# ATMEGA16L-8PI.net
KiCad netlist of a schematic drawn in Altium Designer
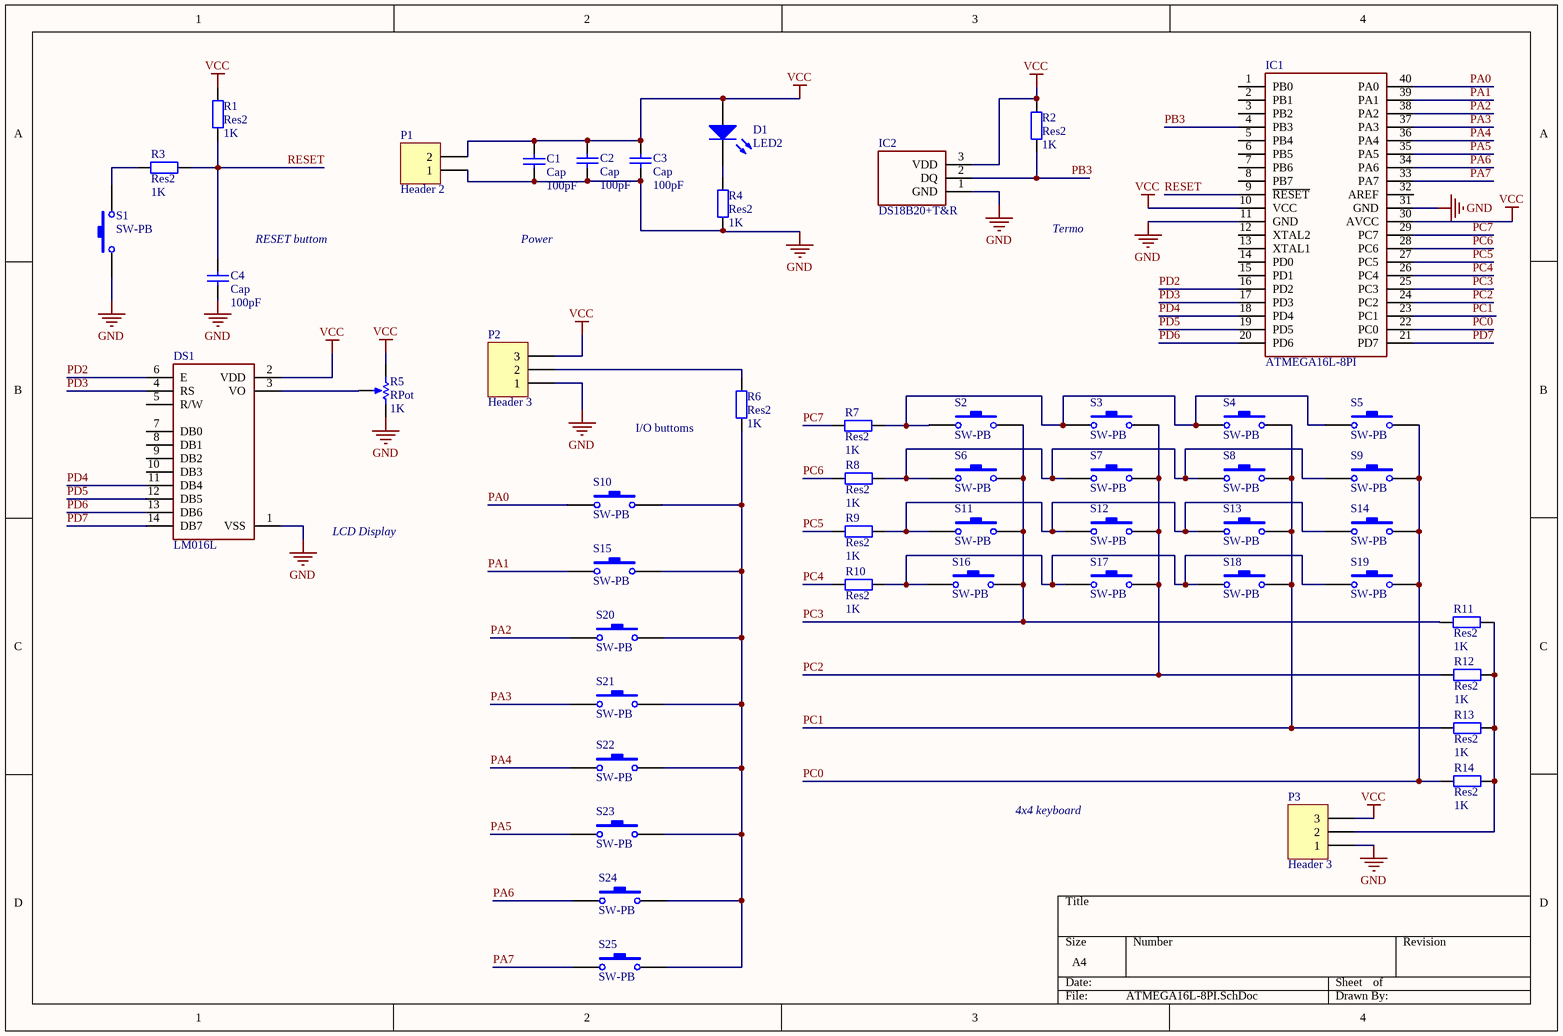
[diagram p0: ATMEGA16L-8PI.SchDoc]

(export (version "E")
  (design (tool "Eeschema 10.0.6"))
  (components
    (comp (ref "C1")
      (value "Cap")
      (footprint "RAD-0.3")
      (description "Capacitor")
      (fields (field (name "ALTIUM_VALUE") "100pF") (field (name "PUBLISHER") "Altium Limited"))
      (libsource (lib "Miscellaneous Devices") (part "Cap"))
    )
    (comp (ref "C2")
      (value "Cap")
      (footprint "RAD-0.3")
      (description "Capacitor")
      (fields (field (name "ALTIUM_VALUE") "100pF") (field (name "PUBLISHER") "Altium Limited"))
      (libsource (lib "Miscellaneous Devices") (part "Cap"))
    )
    (comp (ref "C3")
      (value "Cap")
      (footprint "RAD-0.3")
      (description "Capacitor")
      (fields (field (name "ALTIUM_VALUE") "100pF") (field (name "PUBLISHER") "Altium Limited"))
      (libsource (lib "Miscellaneous Devices") (part "Cap"))
    )
    (comp (ref "C4")
      (value "Cap")
      (footprint "RAD-0.3")
      (description "Capacitor")
      (fields (field (name "ALTIUM_VALUE") "100pF") (field (name "PUBLISHER") "Altium Limited"))
      (libsource (lib "Miscellaneous Devices") (part "Cap"))
    )
    (comp (ref "D1")
      (value "LED2")
      (footprint "3.2X1.6X1.1")
      (description "Typical RED, GREEN, YELLOW, AMBER GaAs LED")
      (fields (field (name "PUBLISHER") "Altium Limited"))
      (libsource (lib "Miscellaneous Devices") (part "LED2"))
    )
    (comp (ref "DS1")
      (value "LM016L")
      (footprint "PcbLib1:LCD_LM016L")
      (description "Display Lcd 35x75mm")
      (fields (field (name "MF") "Hitachi"))
      (libsource (lib "Schlib1") (part "LM016L"))
    )
    (comp (ref "IC1")
      (value "ATMEGA16L-8PI")
      (footprint "PcbLib1:DIP1556W56P254L5232H483Q40N")
      (description "Integrated Circuit")
      (fields (field (name "MOUSER PART NUMBER") "556-ATMEGA16L-8PI"))
      (libsource (lib "Schlib1") (part "ATMEGA16L-8PI"))
    )
    (comp (ref "IC2")
      (value "DS18B20+T&R")
      (footprint "PcbLib1:DS18B20TR")
      (description "Integrated Circuit")
      (fields (field (name "MOUSER PART NUMBER") "700-DS18B20T&R"))
      (libsource (lib "Schlib1") (part "DS18B20+T&R"))
    )
    (comp (ref "P1")
      (value "Header 2")
      (footprint "HDR1X2")
      (description "Header, 2-Pin")
      (fields (field (name "PUBLISHER") "Altium Limited"))
      (libsource (lib "Miscellaneous Connectors") (part "Header 2"))
    )
    (comp (ref "P2")
      (value "Header 3")
      (footprint "HDR1X3")
      (description "Header, 3-Pin")
      (fields (field (name "PUBLISHER") "Altium Limited"))
      (libsource (lib "Miscellaneous Connectors") (part "Header 3"))
    )
    (comp (ref "P3")
      (value "Header 3")
      (footprint "HDR1X3")
      (description "Header, 3-Pin")
      (fields (field (name "PUBLISHER") "Altium Limited"))
      (libsource (lib "Miscellaneous Connectors") (part "Header 3"))
    )
    (comp (ref "R1")
      (value "Res2")
      (footprint "AXIAL-0.4")
      (description "Resistor")
      (fields (field (name "ALTIUM_VALUE") "1K") (field (name "PUBLISHER") "Altium Limited"))
      (libsource (lib "") (part "Res2_1"))
    )
    (comp (ref "R2")
      (value "Res2")
      (footprint "AXIAL-0.4")
      (description "Resistor")
      (fields (field (name "ALTIUM_VALUE") "1K") (field (name "PUBLISHER") "Altium Limited"))
      (libsource (lib "") (part "Res2_1"))
    )
    (comp (ref "R3")
      (value "Res2")
      (footprint "AXIAL-0.4")
      (description "Resistor")
      (fields (field (name "ALTIUM_VALUE") "1K") (field (name "PUBLISHER") "Altium Limited"))
      (libsource (lib "Miscellaneous Devices") (part "Res2"))
    )
    (comp (ref "R4")
      (value "Res2")
      (footprint "AXIAL-0.4")
      (description "Resistor")
      (fields (field (name "ALTIUM_VALUE") "1K") (field (name "PUBLISHER") "Altium Limited"))
      (libsource (lib "") (part "Res2_2"))
    )
    (comp (ref "R5")
      (value "RPot")
      (footprint "VR5")
      (description "Potentiometer")
      (fields (field (name "ALTIUM_VALUE") "1K") (field (name "PUBLISHER") "Altium Limited"))
      (libsource (lib "Miscellaneous Devices") (part "RPot"))
    )
    (comp (ref "R6")
      (value "Res2")
      (footprint "AXIAL-0.4")
      (description "Resistor")
      (fields (field (name "ALTIUM_VALUE") "1K") (field (name "PUBLISHER") "Altium Limited"))
      (libsource (lib "") (part "Res2_1"))
    )
    (comp (ref "R7")
      (value "Res2")
      (footprint "AXIAL-0.4")
      (description "Resistor")
      (fields (field (name "ALTIUM_VALUE") "1K") (field (name "PUBLISHER") "Altium Limited"))
      (libsource (lib "Miscellaneous Devices") (part "Res2"))
    )
    (comp (ref "R8")
      (value "Res2")
      (footprint "AXIAL-0.4")
      (description "Resistor")
      (fields (field (name "ALTIUM_VALUE") "1K") (field (name "PUBLISHER") "Altium Limited"))
      (libsource (lib "Miscellaneous Devices") (part "Res2"))
    )
    (comp (ref "R9")
      (value "Res2")
      (footprint "AXIAL-0.4")
      (description "Resistor")
      (fields (field (name "ALTIUM_VALUE") "1K") (field (name "PUBLISHER") "Altium Limited"))
      (libsource (lib "Miscellaneous Devices") (part "Res2"))
    )
    (comp (ref "R10")
      (value "Res2")
      (footprint "AXIAL-0.4")
      (description "Resistor")
      (fields (field (name "ALTIUM_VALUE") "1K") (field (name "PUBLISHER") "Altium Limited"))
      (libsource (lib "Miscellaneous Devices") (part "Res2"))
    )
    (comp (ref "R11")
      (value "Res2")
      (footprint "AXIAL-0.4")
      (description "Resistor")
      (fields (field (name "ALTIUM_VALUE") "1K") (field (name "PUBLISHER") "Altium Limited"))
      (libsource (lib "Miscellaneous Devices") (part "Res2"))
    )
    (comp (ref "R12")
      (value "Res2")
      (footprint "AXIAL-0.4")
      (description "Resistor")
      (fields (field (name "ALTIUM_VALUE") "1K") (field (name "PUBLISHER") "Altium Limited"))
      (libsource (lib "Miscellaneous Devices") (part "Res2"))
    )
    (comp (ref "R13")
      (value "Res2")
      (footprint "AXIAL-0.4")
      (description "Resistor")
      (fields (field (name "ALTIUM_VALUE") "1K") (field (name "PUBLISHER") "Altium Limited"))
      (libsource (lib "Miscellaneous Devices") (part "Res2"))
    )
    (comp (ref "R14")
      (value "Res2")
      (footprint "AXIAL-0.4")
      (description "Resistor")
      (fields (field (name "ALTIUM_VALUE") "1K") (field (name "PUBLISHER") "Altium Limited"))
      (libsource (lib "Miscellaneous Devices") (part "Res2"))
    )
    (comp (ref "S1")
      (value "SW-PB")
      (footprint "SPST-2")
      (description "Switch")
      (fields (field (name "PUBLISHER") "Altium Limited"))
      (libsource (lib "Miscellaneous Devices") (part "SW-PB"))
    )
    (comp (ref "S2")
      (value "SW-PB")
      (footprint "SPST-2")
      (description "Switch")
      (fields (field (name "PUBLISHER") "Altium Limited"))
      (libsource (lib "Miscellaneous Devices") (part "SW-PB"))
    )
    (comp (ref "S3")
      (value "SW-PB")
      (footprint "SPST-2")
      (description "Switch")
      (fields (field (name "PUBLISHER") "Altium Limited"))
      (libsource (lib "Miscellaneous Devices") (part "SW-PB"))
    )
    (comp (ref "S4")
      (value "SW-PB")
      (footprint "SPST-2")
      (description "Switch")
      (fields (field (name "PUBLISHER") "Altium Limited"))
      (libsource (lib "Miscellaneous Devices") (part "SW-PB"))
    )
    (comp (ref "S5")
      (value "SW-PB")
      (footprint "SPST-2")
      (description "Switch")
      (fields (field (name "PUBLISHER") "Altium Limited"))
      (libsource (lib "Miscellaneous Devices") (part "SW-PB"))
    )
    (comp (ref "S6")
      (value "SW-PB")
      (footprint "SPST-2")
      (description "Switch")
      (fields (field (name "PUBLISHER") "Altium Limited"))
      (libsource (lib "Miscellaneous Devices") (part "SW-PB"))
    )
    (comp (ref "S7")
      (value "SW-PB")
      (footprint "SPST-2")
      (description "Switch")
      (fields (field (name "PUBLISHER") "Altium Limited"))
      (libsource (lib "Miscellaneous Devices") (part "SW-PB"))
    )
    (comp (ref "S8")
      (value "SW-PB")
      (footprint "SPST-2")
      (description "Switch")
      (fields (field (name "PUBLISHER") "Altium Limited"))
      (libsource (lib "Miscellaneous Devices") (part "SW-PB"))
    )
    (comp (ref "S9")
      (value "SW-PB")
      (footprint "SPST-2")
      (description "Switch")
      (fields (field (name "PUBLISHER") "Altium Limited"))
      (libsource (lib "Miscellaneous Devices") (part "SW-PB"))
    )
    (comp (ref "S10")
      (value "SW-PB")
      (footprint "SPST-2")
      (description "Switch")
      (fields (field (name "PUBLISHER") "Altium Limited"))
      (libsource (lib "Miscellaneous Devices") (part "SW-PB"))
    )
    (comp (ref "S11")
      (value "SW-PB")
      (footprint "SPST-2")
      (description "Switch")
      (fields (field (name "PUBLISHER") "Altium Limited"))
      (libsource (lib "Miscellaneous Devices") (part "SW-PB"))
    )
    (comp (ref "S12")
      (value "SW-PB")
      (footprint "SPST-2")
      (description "Switch")
      (fields (field (name "PUBLISHER") "Altium Limited"))
      (libsource (lib "Miscellaneous Devices") (part "SW-PB"))
    )
    (comp (ref "S13")
      (value "SW-PB")
      (footprint "SPST-2")
      (description "Switch")
      (fields (field (name "PUBLISHER") "Altium Limited"))
      (libsource (lib "Miscellaneous Devices") (part "SW-PB"))
    )
    (comp (ref "S14")
      (value "SW-PB")
      (footprint "SPST-2")
      (description "Switch")
      (fields (field (name "PUBLISHER") "Altium Limited"))
      (libsource (lib "Miscellaneous Devices") (part "SW-PB"))
    )
    (comp (ref "S15")
      (value "SW-PB")
      (footprint "SPST-2")
      (description "Switch")
      (fields (field (name "PUBLISHER") "Altium Limited"))
      (libsource (lib "Miscellaneous Devices") (part "SW-PB"))
    )
    (comp (ref "S16")
      (value "SW-PB")
      (footprint "SPST-2")
      (description "Switch")
      (fields (field (name "PUBLISHER") "Altium Limited"))
      (libsource (lib "Miscellaneous Devices") (part "SW-PB"))
    )
    (comp (ref "S17")
      (value "SW-PB")
      (footprint "SPST-2")
      (description "Switch")
      (fields (field (name "PUBLISHER") "Altium Limited"))
      (libsource (lib "Miscellaneous Devices") (part "SW-PB"))
    )
    (comp (ref "S18")
      (value "SW-PB")
      (footprint "SPST-2")
      (description "Switch")
      (fields (field (name "PUBLISHER") "Altium Limited"))
      (libsource (lib "Miscellaneous Devices") (part "SW-PB"))
    )
    (comp (ref "S19")
      (value "SW-PB")
      (footprint "SPST-2")
      (description "Switch")
      (fields (field (name "PUBLISHER") "Altium Limited"))
      (libsource (lib "Miscellaneous Devices") (part "SW-PB"))
    )
    (comp (ref "S20")
      (value "SW-PB")
      (footprint "SPST-2")
      (description "Switch")
      (fields (field (name "PUBLISHER") "Altium Limited"))
      (libsource (lib "Miscellaneous Devices") (part "SW-PB"))
    )
    (comp (ref "S21")
      (value "SW-PB")
      (footprint "SPST-2")
      (description "Switch")
      (fields (field (name "PUBLISHER") "Altium Limited"))
      (libsource (lib "Miscellaneous Devices") (part "SW-PB"))
    )
    (comp (ref "S22")
      (value "SW-PB")
      (footprint "SPST-2")
      (description "Switch")
      (fields (field (name "PUBLISHER") "Altium Limited"))
      (libsource (lib "Miscellaneous Devices") (part "SW-PB"))
    )
    (comp (ref "S23")
      (value "SW-PB")
      (footprint "SPST-2")
      (description "Switch")
      (fields (field (name "PUBLISHER") "Altium Limited"))
      (libsource (lib "Miscellaneous Devices") (part "SW-PB"))
    )
    (comp (ref "S24")
      (value "SW-PB")
      (footprint "SPST-2")
      (description "Switch")
      (fields (field (name "PUBLISHER") "Altium Limited"))
      (libsource (lib "Miscellaneous Devices") (part "SW-PB"))
    )
    (comp (ref "S25")
      (value "SW-PB")
      (footprint "SPST-2")
      (description "Switch")
      (fields (field (name "PUBLISHER") "Altium Limited"))
      (libsource (lib "Miscellaneous Devices") (part "SW-PB"))
    )
  )
  (nets
    (net (code "1") (name "/PA0") (class "Default")
      (node (ref "IC1") (pin "40") (pinfunction "PA0_40") (pintype "passive"))
      (node (ref "S10") (pin "1") (pinfunction "1_1") (pintype "passive"))
    )
    (net (code "2") (name "/PA1") (class "Default")
      (node (ref "IC1") (pin "39") (pinfunction "PA1_39") (pintype "passive"))
      (node (ref "S15") (pin "1") (pinfunction "1_1") (pintype "passive"))
    )
    (net (code "3") (name "/PA2") (class "Default")
      (node (ref "IC1") (pin "38") (pinfunction "PA2_38") (pintype "passive"))
      (node (ref "S20") (pin "1") (pinfunction "1_1") (pintype "passive"))
    )
    (net (code "4") (name "/PA3") (class "Default")
      (node (ref "IC1") (pin "37") (pinfunction "PA3_37") (pintype "passive"))
      (node (ref "S21") (pin "1") (pinfunction "1_1") (pintype "passive"))
    )
    (net (code "5") (name "/PA4") (class "Default")
      (node (ref "IC1") (pin "36") (pinfunction "PA4_36") (pintype "passive"))
      (node (ref "S22") (pin "1") (pinfunction "1_1") (pintype "passive"))
    )
    (net (code "6") (name "/PA5") (class "Default")
      (node (ref "IC1") (pin "35") (pinfunction "PA5_35") (pintype "passive"))
      (node (ref "S23") (pin "1") (pinfunction "1_1") (pintype "passive"))
    )
    (net (code "7") (name "/PA6") (class "Default")
      (node (ref "IC1") (pin "34") (pinfunction "PA6_34") (pintype "passive"))
      (node (ref "S24") (pin "1") (pinfunction "1_1") (pintype "passive"))
    )
    (net (code "8") (name "/PA7") (class "Default")
      (node (ref "IC1") (pin "33") (pinfunction "PA7_33") (pintype "passive"))
      (node (ref "S25") (pin "1") (pinfunction "1_1") (pintype "passive"))
    )
    (net (code "9") (name "/PB3") (class "Default")
      (node (ref "IC1") (pin "4") (pinfunction "PB3_4") (pintype "passive"))
      (node (ref "IC2") (pin "2") (pinfunction "DQ_2") (pintype "passive"))
      (node (ref "R2") (pin "1") (pinfunction "1_1") (pintype "passive"))
    )
    (net (code "10") (name "/PC0") (class "Default")
      (node (ref "IC1") (pin "22") (pinfunction "PC0_22") (pintype "passive"))
      (node (ref "R14") (pin "2") (pinfunction "2_2") (pintype "passive"))
      (node (ref "S14") (pin "2") (pinfunction "2_2") (pintype "passive"))
      (node (ref "S19") (pin "2") (pinfunction "2_2") (pintype "passive"))
      (node (ref "S5") (pin "2") (pinfunction "2_2") (pintype "passive"))
      (node (ref "S9") (pin "2") (pinfunction "2_2") (pintype "passive"))
    )
    (net (code "11") (name "/PC1") (class "Default")
      (node (ref "IC1") (pin "23") (pinfunction "PC1_23") (pintype "passive"))
      (node (ref "R13") (pin "2") (pinfunction "2_2") (pintype "passive"))
      (node (ref "S13") (pin "2") (pinfunction "2_2") (pintype "passive"))
      (node (ref "S18") (pin "2") (pinfunction "2_2") (pintype "passive"))
      (node (ref "S4") (pin "2") (pinfunction "2_2") (pintype "passive"))
      (node (ref "S8") (pin "2") (pinfunction "2_2") (pintype "passive"))
    )
    (net (code "12") (name "/PC2") (class "Default")
      (node (ref "IC1") (pin "24") (pinfunction "PC2_24") (pintype "passive"))
      (node (ref "R12") (pin "2") (pinfunction "2_2") (pintype "passive"))
      (node (ref "S12") (pin "2") (pinfunction "2_2") (pintype "passive"))
      (node (ref "S17") (pin "2") (pinfunction "2_2") (pintype "passive"))
      (node (ref "S3") (pin "2") (pinfunction "2_2") (pintype "passive"))
      (node (ref "S7") (pin "2") (pinfunction "2_2") (pintype "passive"))
    )
    (net (code "13") (name "/PC3") (class "Default")
      (node (ref "IC1") (pin "25") (pinfunction "PC3_25") (pintype "passive"))
      (node (ref "R11") (pin "2") (pinfunction "2_2") (pintype "passive"))
      (node (ref "S11") (pin "2") (pinfunction "2_2") (pintype "passive"))
      (node (ref "S16") (pin "2") (pinfunction "2_2") (pintype "passive"))
      (node (ref "S2") (pin "2") (pinfunction "2_2") (pintype "passive"))
      (node (ref "S6") (pin "2") (pinfunction "2_2") (pintype "passive"))
    )
    (net (code "14") (name "/PC4") (class "Default")
      (node (ref "IC1") (pin "26") (pinfunction "PC4_26") (pintype "passive"))
      (node (ref "R10") (pin "2") (pinfunction "2_2") (pintype "passive"))
    )
    (net (code "15") (name "/PC5") (class "Default")
      (node (ref "IC1") (pin "27") (pinfunction "PC5_27") (pintype "passive"))
      (node (ref "R9") (pin "2") (pinfunction "2_2") (pintype "passive"))
    )
    (net (code "16") (name "/PC6") (class "Default")
      (node (ref "IC1") (pin "28") (pinfunction "PC6_28") (pintype "passive"))
      (node (ref "R8") (pin "2") (pinfunction "2_2") (pintype "passive"))
    )
    (net (code "17") (name "/PC7") (class "Default")
      (node (ref "IC1") (pin "29") (pinfunction "PC7_29") (pintype "passive"))
      (node (ref "R7") (pin "2") (pinfunction "2_2") (pintype "passive"))
    )
    (net (code "18") (name "/PD2") (class "Default")
      (node (ref "DS1") (pin "6") (pinfunction "E_6") (pintype "passive"))
      (node (ref "IC1") (pin "16") (pinfunction "PD2_16") (pintype "passive"))
    )
    (net (code "19") (name "/PD3") (class "Default")
      (node (ref "DS1") (pin "4") (pinfunction "RS_4") (pintype "passive"))
      (node (ref "IC1") (pin "17") (pinfunction "PD3_17") (pintype "passive"))
    )
    (net (code "20") (name "/PD4") (class "Default")
      (node (ref "DS1") (pin "11") (pinfunction "DB4_11") (pintype "passive"))
      (node (ref "IC1") (pin "18") (pinfunction "PD4_18") (pintype "passive"))
    )
    (net (code "21") (name "/PD5") (class "Default")
      (node (ref "DS1") (pin "12") (pinfunction "DB5_12") (pintype "passive"))
      (node (ref "IC1") (pin "19") (pinfunction "PD5_19") (pintype "passive"))
    )
    (net (code "22") (name "/PD6") (class "Default")
      (node (ref "DS1") (pin "13") (pinfunction "DB6_13") (pintype "passive"))
      (node (ref "IC1") (pin "20") (pinfunction "PD6_20") (pintype "passive"))
    )
    (net (code "23") (name "/PD7") (class "Default")
      (node (ref "DS1") (pin "14") (pinfunction "DB7_14") (pintype "passive"))
      (node (ref "IC1") (pin "21") (pinfunction "PD7_21") (pintype "passive"))
    )
    (net (code "24") (name "/RESET") (class "Default")
      (node (ref "C4") (pin "2") (pinfunction "2_2") (pintype "passive"))
      (node (ref "IC1") (pin "9") (pinfunction "~{RESET}_9") (pintype "passive"))
      (node (ref "R1") (pin "1") (pinfunction "1_1") (pintype "passive"))
      (node (ref "R3") (pin "1") (pinfunction "1_1") (pintype "passive"))
    )
    (net (code "25") (name "GND") (class "Default")
      (node (ref "C1") (pin "1") (pinfunction "1_1") (pintype "passive"))
      (node (ref "C2") (pin "1") (pinfunction "1_1") (pintype "passive"))
      (node (ref "C3") (pin "1") (pinfunction "1_1") (pintype "passive"))
      (node (ref "C4") (pin "1") (pinfunction "1_1") (pintype "passive"))
      (node (ref "DS1") (pin "1") (pinfunction "VSS_1") (pintype "power_in"))
      (node (ref "IC1") (pin "11") (pinfunction "GND_11") (pintype "passive"))
      (node (ref "IC1") (pin "31") (pinfunction "GND_31") (pintype "passive"))
      (node (ref "IC2") (pin "1") (pinfunction "GND_1") (pintype "passive"))
      (node (ref "P1") (pin "1") (pinfunction "1_1") (pintype "passive"))
      (node (ref "P2") (pin "1") (pinfunction "1_1") (pintype "passive"))
      (node (ref "P3") (pin "1") (pinfunction "1_1") (pintype "passive"))
      (node (ref "R4") (pin "2") (pinfunction "2_2") (pintype "passive"))
      (node (ref "R5") (pin "2") (pinfunction "BOT_2") (pintype "passive"))
      (node (ref "S1") (pin "1") (pinfunction "1_1") (pintype "passive"))
    )
    (net (code "26") (name "Net-(D1-K)") (class "Default")
      (node (ref "D1") (pin "2") (pinfunction "K_2") (pintype "passive"))
      (node (ref "R4") (pin "1") (pinfunction "1_1") (pintype "passive"))
    )
    (net (code "27") (name "Net-(DS1-VO)") (class "Default")
      (node (ref "DS1") (pin "3") (pinfunction "VO_3") (pintype "power_in"))
      (node (ref "R5") (pin "3") (pinfunction "TAP_3") (pintype "passive"))
    )
    (net (code "28") (name "Net-(P2-Pad2)") (class "Default")
      (node (ref "P2") (pin "2") (pinfunction "2_2") (pintype "passive"))
      (node (ref "R6") (pin "2") (pinfunction "2_2") (pintype "passive"))
    )
    (net (code "29") (name "Net-(P3-Pad2)") (class "Default")
      (node (ref "P3") (pin "2") (pinfunction "2_2") (pintype "passive"))
      (node (ref "R11") (pin "1") (pinfunction "1_1") (pintype "passive"))
      (node (ref "R12") (pin "1") (pinfunction "1_1") (pintype "passive"))
      (node (ref "R13") (pin "1") (pinfunction "1_1") (pintype "passive"))
      (node (ref "R14") (pin "1") (pinfunction "1_1") (pintype "passive"))
    )
    (net (code "30") (name "Net-(R3-Pad2)") (class "Default")
      (node (ref "R3") (pin "2") (pinfunction "2_2") (pintype "passive"))
      (node (ref "S1") (pin "2") (pinfunction "2_2") (pintype "passive"))
    )
    (net (code "31") (name "Net-(R6-Pad1)") (class "Default")
      (node (ref "R6") (pin "1") (pinfunction "1_1") (pintype "passive"))
      (node (ref "S10") (pin "2") (pinfunction "2_2") (pintype "passive"))
      (node (ref "S15") (pin "2") (pinfunction "2_2") (pintype "passive"))
      (node (ref "S20") (pin "2") (pinfunction "2_2") (pintype "passive"))
      (node (ref "S21") (pin "2") (pinfunction "2_2") (pintype "passive"))
      (node (ref "S22") (pin "2") (pinfunction "2_2") (pintype "passive"))
      (node (ref "S23") (pin "2") (pinfunction "2_2") (pintype "passive"))
      (node (ref "S24") (pin "2") (pinfunction "2_2") (pintype "passive"))
      (node (ref "S25") (pin "2") (pinfunction "2_2") (pintype "passive"))
    )
    (net (code "32") (name "Net-(R7-Pad1)") (class "Default")
      (node (ref "R7") (pin "1") (pinfunction "1_1") (pintype "passive"))
      (node (ref "S2") (pin "1") (pinfunction "1_1") (pintype "passive"))
      (node (ref "S3") (pin "1") (pinfunction "1_1") (pintype "passive"))
      (node (ref "S4") (pin "1") (pinfunction "1_1") (pintype "passive"))
      (node (ref "S5") (pin "1") (pinfunction "1_1") (pintype "passive"))
    )
    (net (code "33") (name "Net-(R8-Pad1)") (class "Default")
      (node (ref "R8") (pin "1") (pinfunction "1_1") (pintype "passive"))
      (node (ref "S6") (pin "1") (pinfunction "1_1") (pintype "passive"))
      (node (ref "S7") (pin "1") (pinfunction "1_1") (pintype "passive"))
      (node (ref "S8") (pin "1") (pinfunction "1_1") (pintype "passive"))
      (node (ref "S9") (pin "1") (pinfunction "1_1") (pintype "passive"))
    )
    (net (code "34") (name "Net-(R9-Pad1)") (class "Default")
      (node (ref "R9") (pin "1") (pinfunction "1_1") (pintype "passive"))
      (node (ref "S11") (pin "1") (pinfunction "1_1") (pintype "passive"))
      (node (ref "S12") (pin "1") (pinfunction "1_1") (pintype "passive"))
      (node (ref "S13") (pin "1") (pinfunction "1_1") (pintype "passive"))
      (node (ref "S14") (pin "1") (pinfunction "1_1") (pintype "passive"))
    )
    (net (code "35") (name "Net-(R10-Pad1)") (class "Default")
      (node (ref "R10") (pin "1") (pinfunction "1_1") (pintype "passive"))
      (node (ref "S16") (pin "1") (pinfunction "1_1") (pintype "passive"))
      (node (ref "S17") (pin "1") (pinfunction "1_1") (pintype "passive"))
      (node (ref "S18") (pin "1") (pinfunction "1_1") (pintype "passive"))
      (node (ref "S19") (pin "1") (pinfunction "1_1") (pintype "passive"))
    )
    (net (code "36") (name "VCC") (class "Default")
      (node (ref "C1") (pin "2") (pinfunction "2_2") (pintype "passive"))
      (node (ref "C2") (pin "2") (pinfunction "2_2") (pintype "passive"))
      (node (ref "C3") (pin "2") (pinfunction "2_2") (pintype "passive"))
      (node (ref "D1") (pin "1") (pinfunction "A_1") (pintype "passive"))
      (node (ref "DS1") (pin "2") (pinfunction "VDD_2") (pintype "power_in"))
      (node (ref "IC1") (pin "10") (pinfunction "VCC_10") (pintype "passive"))
      (node (ref "IC1") (pin "30") (pinfunction "AVCC_30") (pintype "passive"))
      (node (ref "IC2") (pin "3") (pinfunction "VDD_3") (pintype "passive"))
      (node (ref "P1") (pin "2") (pinfunction "2_2") (pintype "passive"))
      (node (ref "P2") (pin "3") (pinfunction "3_3") (pintype "passive"))
      (node (ref "P3") (pin "3") (pinfunction "3_3") (pintype "passive"))
      (node (ref "R1") (pin "2") (pinfunction "2_2") (pintype "passive"))
      (node (ref "R2") (pin "2") (pinfunction "2_2") (pintype "passive"))
      (node (ref "R5") (pin "1") (pinfunction "TOP_1") (pintype "passive"))
    )
    (net (code "37") (name "unconnected-(DS1-DB0-Pad7)") (class "Default")
      (node (ref "DS1") (pin "7") (pinfunction "DB0_7") (pintype "passive"))
    )
    (net (code "38") (name "unconnected-(DS1-DB1-Pad8)") (class "Default")
      (node (ref "DS1") (pin "8") (pinfunction "DB1_8") (pintype "passive"))
    )
    (net (code "39") (name "unconnected-(DS1-DB2-Pad9)") (class "Default")
      (node (ref "DS1") (pin "9") (pinfunction "DB2_9") (pintype "passive"))
    )
    (net (code "40") (name "unconnected-(DS1-DB3-Pad10)") (class "Default")
      (node (ref "DS1") (pin "10") (pinfunction "DB3_10") (pintype "passive"))
    )
    (net (code "41") (name "unconnected-(DS1-R{slash}W-Pad5)") (class "Default")
      (node (ref "DS1") (pin "5") (pinfunction "R/W_5") (pintype "passive"))
    )
    (net (code "42") (name "unconnected-(IC1-AREF-Pad32)") (class "Default")
      (node (ref "IC1") (pin "32") (pinfunction "AREF_32") (pintype "passive"))
    )
    (net (code "43") (name "unconnected-(IC1-PB0-Pad1)") (class "Default")
      (node (ref "IC1") (pin "1") (pinfunction "PB0_1") (pintype "passive"))
    )
    (net (code "44") (name "unconnected-(IC1-PB1-Pad2)") (class "Default")
      (node (ref "IC1") (pin "2") (pinfunction "PB1_2") (pintype "passive"))
    )
    (net (code "45") (name "unconnected-(IC1-PB2-Pad3)") (class "Default")
      (node (ref "IC1") (pin "3") (pinfunction "PB2_3") (pintype "passive"))
    )
    (net (code "46") (name "unconnected-(IC1-PB4-Pad5)") (class "Default")
      (node (ref "IC1") (pin "5") (pinfunction "PB4_5") (pintype "passive"))
    )
    (net (code "47") (name "unconnected-(IC1-PB5-Pad6)") (class "Default")
      (node (ref "IC1") (pin "6") (pinfunction "PB5_6") (pintype "passive"))
    )
    (net (code "48") (name "unconnected-(IC1-PB6-Pad7)") (class "Default")
      (node (ref "IC1") (pin "7") (pinfunction "PB6_7") (pintype "passive"))
    )
    (net (code "49") (name "unconnected-(IC1-PB7-Pad8)") (class "Default")
      (node (ref "IC1") (pin "8") (pinfunction "PB7_8") (pintype "passive"))
    )
    (net (code "50") (name "unconnected-(IC1-PD0-Pad14)") (class "Default")
      (node (ref "IC1") (pin "14") (pinfunction "PD0_14") (pintype "passive"))
    )
    (net (code "51") (name "unconnected-(IC1-PD1-Pad15)") (class "Default")
      (node (ref "IC1") (pin "15") (pinfunction "PD1_15") (pintype "passive"))
    )
    (net (code "52") (name "unconnected-(IC1-XTAL1-Pad13)") (class "Default")
      (node (ref "IC1") (pin "13") (pinfunction "XTAL1_13") (pintype "passive"))
    )
    (net (code "53") (name "unconnected-(IC1-XTAL2-Pad12)") (class "Default")
      (node (ref "IC1") (pin "12") (pinfunction "XTAL2_12") (pintype "passive"))
    )
  )
)
